# HighPowerWS2801_v2.net
KiCad netlist of a schematic drawn in EAGLE
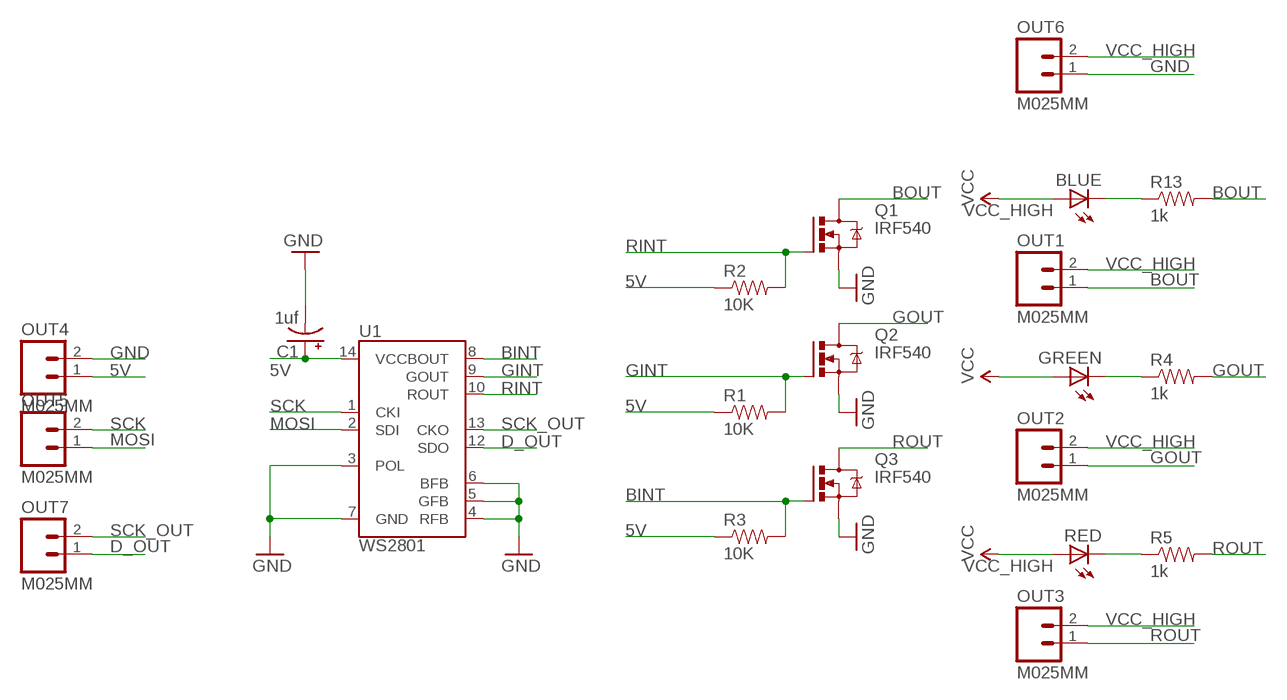
[diagram p0: schematic, sheet 1]

(export (version "E")
  (design (tool "Eeschema 10.0.6"))
  (components
    (comp (ref "BLUE")
      (value "LED3MM")
      (footprint "eagle-import:LED3MM")
      (libsource (lib "eagle-import") (part "LED3MM"))
    )
    (comp (ref "C1")
      (value "1uf")
      (footprint "eagle-import:CPOL-RADIAL-10UF-25V")
      (libsource (lib "eagle-import") (part "10UF-25V-20%(PTH)"))
    )
    (comp (ref "GREEN")
      (value "LED3MM")
      (footprint "eagle-import:LED3MM")
      (libsource (lib "eagle-import") (part "LED3MM"))
    )
    (comp (ref "OUT1")
      (value "M025MM")
      (footprint "eagle-import:SCREWTERMINAL-5MM-2")
      (libsource (lib "eagle-import") (part "M025MM"))
    )
    (comp (ref "OUT2")
      (value "M025MM")
      (footprint "eagle-import:SCREWTERMINAL-5MM-2")
      (libsource (lib "eagle-import") (part "M025MM"))
    )
    (comp (ref "OUT3")
      (value "M025MM")
      (footprint "eagle-import:SCREWTERMINAL-5MM-2")
      (libsource (lib "eagle-import") (part "M025MM"))
    )
    (comp (ref "OUT4")
      (value "M025MM")
      (footprint "eagle-import:SCREWTERMINAL-5MM-2")
      (libsource (lib "eagle-import") (part "M025MM"))
    )
    (comp (ref "OUT5")
      (value "M025MM")
      (footprint "eagle-import:SCREWTERMINAL-5MM-2")
      (libsource (lib "eagle-import") (part "M025MM"))
    )
    (comp (ref "OUT6")
      (value "M025MM")
      (footprint "eagle-import:SCREWTERMINAL-5MM-2")
      (libsource (lib "eagle-import") (part "M025MM"))
    )
    (comp (ref "OUT7")
      (value "M025MM")
      (footprint "eagle-import:SCREWTERMINAL-5MM-2")
      (libsource (lib "eagle-import") (part "M025MM"))
    )
    (comp (ref "Q1")
      (value "IRF540")
      (footprint "eagle-import:TO220BV")
      (libsource (lib "eagle-import") (part "IRF540"))
    )
    (comp (ref "Q2")
      (value "IRF540")
      (footprint "eagle-import:TO220BV")
      (libsource (lib "eagle-import") (part "IRF540"))
    )
    (comp (ref "Q3")
      (value "IRF540")
      (footprint "eagle-import:TO220BV")
      (libsource (lib "eagle-import") (part "IRF540"))
    )
    (comp (ref "R1")
      (value "10K")
      (footprint "eagle-import:AXIAL-0.4")
      (libsource (lib "eagle-import") (part "RESISTORPTH-1/4W"))
    )
    (comp (ref "R2")
      (value "10K")
      (footprint "eagle-import:AXIAL-0.4")
      (libsource (lib "eagle-import") (part "RESISTORPTH-1/4W"))
    )
    (comp (ref "R3")
      (value "10K")
      (footprint "eagle-import:AXIAL-0.4")
      (libsource (lib "eagle-import") (part "RESISTORPTH-1/4W"))
    )
    (comp (ref "R4")
      (value "1k")
      (footprint "eagle-import:AXIAL-0.4")
      (libsource (lib "eagle-import") (part "RESISTORPTH-1/4W"))
    )
    (comp (ref "R5")
      (value "1k")
      (footprint "eagle-import:AXIAL-0.4")
      (libsource (lib "eagle-import") (part "RESISTORPTH-1/4W"))
    )
    (comp (ref "R13")
      (value "1k")
      (footprint "eagle-import:AXIAL-0.4")
      (libsource (lib "eagle-import") (part "RESISTORPTH-1/4W"))
    )
    (comp (ref "RED")
      (value "LED3MM")
      (footprint "eagle-import:LED3MM")
      (libsource (lib "eagle-import") (part "LED3MM"))
    )
    (comp (ref "U1")
      (value "WS2801")
      (footprint "eagle-import:SOP-14")
      (libsource (lib "eagle-import") (part "WS2801"))
    )
  )
  (nets
    (net (code "1") (name "/5V") (class "Default")
      (node (ref "C1") (pin "1") (pinfunction "+_1") (pintype "passive"))
      (node (ref "OUT4") (pin "1") (pinfunction "1_1") (pintype "passive"))
      (node (ref "R1") (pin "P$1") (pinfunction "1_P$1") (pintype "passive"))
      (node (ref "R2") (pin "P$1") (pinfunction "1_P$1") (pintype "passive"))
      (node (ref "R3") (pin "P$1") (pinfunction "1_P$1") (pintype "passive"))
      (node (ref "U1") (pin "14") (pinfunction "VCC_14") (pintype "bidirectional"))
    )
    (net (code "2") (name "/BINT") (class "Default")
      (node (ref "Q3") (pin "G") (pinfunction "G_G") (pintype "passive"))
      (node (ref "R3") (pin "P$2") (pinfunction "2_P$2") (pintype "passive"))
      (node (ref "U1") (pin "8") (pinfunction "BOUT_8") (pintype "bidirectional"))
    )
    (net (code "3") (name "/BOUT") (class "Default")
      (node (ref "OUT1") (pin "1") (pinfunction "1_1") (pintype "passive"))
      (node (ref "Q1") (pin "D") (pinfunction "D_D") (pintype "passive"))
      (node (ref "R13") (pin "P$2") (pinfunction "2_P$2") (pintype "passive"))
    )
    (net (code "4") (name "/D_OUT") (class "Default")
      (node (ref "OUT7") (pin "1") (pinfunction "1_1") (pintype "passive"))
      (node (ref "U1") (pin "12") (pinfunction "SDO_12") (pintype "bidirectional"))
    )
    (net (code "5") (name "/GINT") (class "Default")
      (node (ref "Q2") (pin "G") (pinfunction "G_G") (pintype "passive"))
      (node (ref "R1") (pin "P$2") (pinfunction "2_P$2") (pintype "passive"))
      (node (ref "U1") (pin "9") (pinfunction "GOUT_9") (pintype "bidirectional"))
    )
    (net (code "6") (name "/GOUT") (class "Default")
      (node (ref "OUT2") (pin "1") (pinfunction "1_1") (pintype "passive"))
      (node (ref "Q2") (pin "D") (pinfunction "D_D") (pintype "passive"))
      (node (ref "R4") (pin "P$2") (pinfunction "2_P$2") (pintype "passive"))
    )
    (net (code "7") (name "/MOSI") (class "Default")
      (node (ref "OUT5") (pin "1") (pinfunction "1_1") (pintype "passive"))
      (node (ref "U1") (pin "2") (pinfunction "SDI_2") (pintype "bidirectional"))
    )
    (net (code "8") (name "/RINT") (class "Default")
      (node (ref "Q1") (pin "G") (pinfunction "G_G") (pintype "passive"))
      (node (ref "R2") (pin "P$2") (pinfunction "2_P$2") (pintype "passive"))
      (node (ref "U1") (pin "10") (pinfunction "ROUT_10") (pintype "bidirectional"))
    )
    (net (code "9") (name "/ROUT") (class "Default")
      (node (ref "OUT3") (pin "1") (pinfunction "1_1") (pintype "passive"))
      (node (ref "Q3") (pin "D") (pinfunction "D_D") (pintype "passive"))
      (node (ref "R5") (pin "P$2") (pinfunction "2_P$2") (pintype "passive"))
    )
    (net (code "10") (name "/SCK") (class "Default")
      (node (ref "OUT5") (pin "2") (pinfunction "2_2") (pintype "passive"))
      (node (ref "U1") (pin "1") (pinfunction "CKI_1") (pintype "bidirectional"))
    )
    (net (code "11") (name "/SCK_OUT") (class "Default")
      (node (ref "OUT7") (pin "2") (pinfunction "2_2") (pintype "passive"))
      (node (ref "U1") (pin "13") (pinfunction "CKO_13") (pintype "bidirectional"))
    )
    (net (code "12") (name "GND") (class "Default")
      (node (ref "C1") (pin "2") (pinfunction "-_2") (pintype "passive"))
      (node (ref "OUT4") (pin "2") (pinfunction "2_2") (pintype "passive"))
      (node (ref "OUT6") (pin "1") (pinfunction "1_1") (pintype "passive"))
      (node (ref "Q1") (pin "S") (pinfunction "S_S") (pintype "passive"))
      (node (ref "Q2") (pin "S") (pinfunction "S_S") (pintype "passive"))
      (node (ref "Q3") (pin "S") (pinfunction "S_S") (pintype "passive"))
      (node (ref "U1") (pin "3") (pinfunction "POL_3") (pintype "bidirectional"))
      (node (ref "U1") (pin "4") (pinfunction "RFB_4") (pintype "bidirectional"))
      (node (ref "U1") (pin "5") (pinfunction "GFB_5") (pintype "bidirectional"))
      (node (ref "U1") (pin "6") (pinfunction "BFB_6") (pintype "bidirectional"))
      (node (ref "U1") (pin "7") (pinfunction "GND_7") (pintype "bidirectional"))
    )
    (net (code "13") (name "Net-(BLUE-C)") (class "Default")
      (node (ref "BLUE") (pin "K") (pinfunction "C_K") (pintype "passive"))
      (node (ref "R13") (pin "P$1") (pinfunction "1_P$1") (pintype "passive"))
    )
    (net (code "14") (name "Net-(GREEN-C)") (class "Default")
      (node (ref "GREEN") (pin "K") (pinfunction "C_K") (pintype "passive"))
      (node (ref "R4") (pin "P$1") (pinfunction "1_P$1") (pintype "passive"))
    )
    (net (code "15") (name "Net-(R5-1)") (class "Default")
      (node (ref "R5") (pin "P$1") (pinfunction "1_P$1") (pintype "passive"))
      (node (ref "RED") (pin "K") (pinfunction "C_K") (pintype "passive"))
    )
    (net (code "16") (name "VCC") (class "Default")
      (node (ref "BLUE") (pin "A") (pinfunction "A_A") (pintype "passive"))
      (node (ref "GREEN") (pin "A") (pinfunction "A_A") (pintype "passive"))
      (node (ref "OUT1") (pin "2") (pinfunction "2_2") (pintype "passive"))
      (node (ref "OUT2") (pin "2") (pinfunction "2_2") (pintype "passive"))
      (node (ref "OUT3") (pin "2") (pinfunction "2_2") (pintype "passive"))
      (node (ref "OUT6") (pin "2") (pinfunction "2_2") (pintype "passive"))
      (node (ref "RED") (pin "A") (pinfunction "A_A") (pintype "passive"))
    )
  )
)
